# MotorDriver_Schematics.net
KiCad netlist of a schematic drawn in Altium Designer
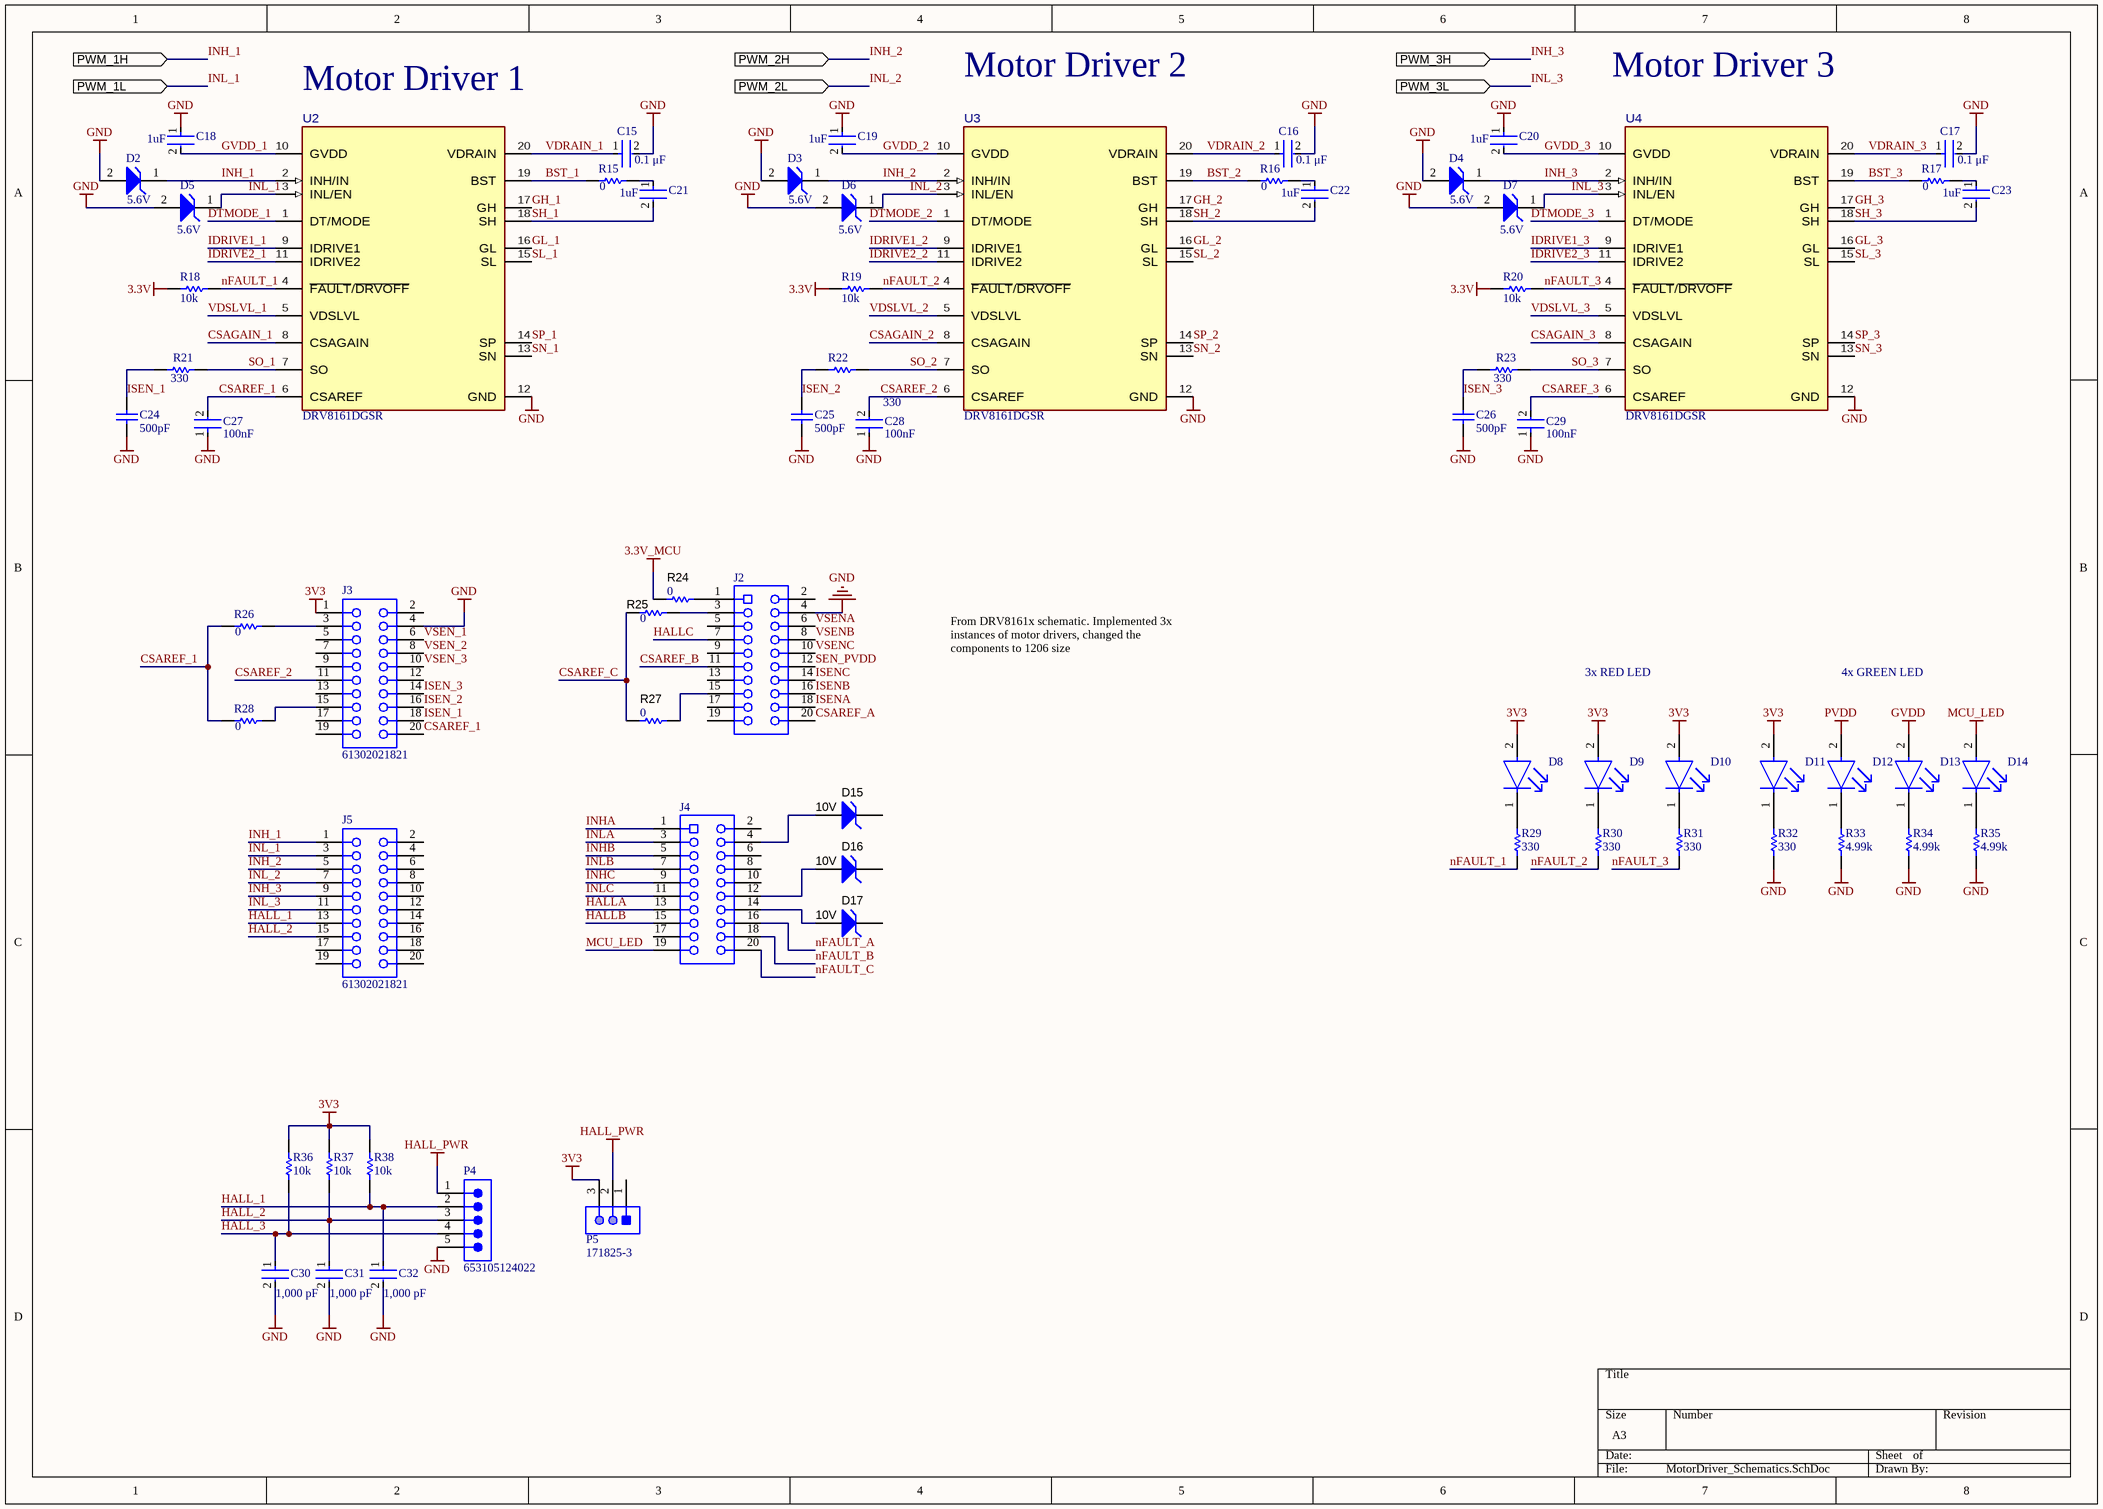
[diagram p0: MotorDriver_Schematics.SchDoc]

(export (version "E")
  (design (tool "Eeschema 10.0.6"))
  (components
    (comp (ref "C15")
      (value "C1206C104K1RACTU")
      (footprint "FP-C1206C-EB-MFG")
      (description "CAP CER 0.1UF 100V X7R 1206")
      (fields
        (field (name "TOLERANCE") "0.1")
        (field (name "OCTOPART") "https://octopart.com/c1206c104k1ractu-kemet-89521")
        (field (name "CAPACITANCE") "0.1 μF")
      )
      (libsource (lib "Altium Content Vault") (part "b4654b650e69147ec39a6b967a45e02"))
    )
    (comp (ref "C16")
      (value "C1206C104K1RACTU")
      (footprint "FP-C1206C-EB-MFG")
      (description "CAP CER 0.1UF 100V X7R 1206")
      (fields
        (field (name "TOLERANCE") "0.1")
        (field (name "OCTOPART") "https://octopart.com/c1206c104k1ractu-kemet-89521")
        (field (name "CAPACITANCE") "0.1 μF")
      )
      (libsource (lib "Altium Content Vault") (part "b4654b650e69147ec39a6b967a45e02"))
    )
    (comp (ref "C17")
      (value "C1206C104K1RACTU")
      (footprint "FP-C1206C-EB-MFG")
      (description "CAP CER 0.1UF 100V X7R 1206")
      (fields
        (field (name "TOLERANCE") "0.1")
        (field (name "OCTOPART") "https://octopart.com/c1206c104k1ractu-kemet-89521")
        (field (name "CAPACITANCE") "0.1 μF")
      )
      (libsource (lib "Altium Content Vault") (part "b4654b650e69147ec39a6b967a45e02"))
    )
    (comp (ref "C18")
      (value "12063C105KAT2A")
      (footprint "FP-1206-L_3_2_0_2-W_1_6_0-IPC_A")
      (description "General Purpose Ceramic Capacitor, 1206, 1uF, 10%, X7R, 15%, 25V")
      (fields
        (field (name "CAPACITANCE") "1uF")
        (field (name "TOLERANCE") "10%")
        (field (name "VOLTAGE") "25V")
      )
      (libsource (lib "Altium Content Vault") (part "b4654b650e69147ec39a6b967a45e02"))
    )
    (comp (ref "C19")
      (value "12063C105KAT2A")
      (footprint "FP-1206-L_3_2_0_2-W_1_6_0-IPC_A")
      (description "General Purpose Ceramic Capacitor, 1206, 1uF, 10%, X7R, 15%, 25V")
      (fields
        (field (name "CAPACITANCE") "1uF")
        (field (name "TOLERANCE") "10%")
        (field (name "VOLTAGE") "25V")
      )
      (libsource (lib "Altium Content Vault") (part "b4654b650e69147ec39a6b967a45e02"))
    )
    (comp (ref "C20")
      (value "12063C105KAT2A")
      (footprint "FP-1206-L_3_2_0_2-W_1_6_0-IPC_A")
      (description "General Purpose Ceramic Capacitor, 1206, 1uF, 10%, X7R, 15%, 25V")
      (fields
        (field (name "CAPACITANCE") "1uF")
        (field (name "TOLERANCE") "10%")
        (field (name "VOLTAGE") "25V")
      )
      (libsource (lib "Altium Content Vault") (part "b4654b650e69147ec39a6b967a45e02"))
    )
    (comp (ref "C21")
      (value "12063C105KAT2A")
      (footprint "FP-1206-L_3_2_0_2-W_1_6_0-IPC_A")
      (description "General Purpose Ceramic Capacitor, 1206, 1uF, 10%, X7R, 15%, 25V")
      (fields
        (field (name "CAPACITANCE") "1uF")
        (field (name "TOLERANCE") "10%")
        (field (name "VOLTAGE") "25V")
      )
      (libsource (lib "Altium Content Vault") (part "b4654b650e69147ec39a6b967a45e02"))
    )
    (comp (ref "C22")
      (value "12063C105KAT2A")
      (footprint "FP-1206-L_3_2_0_2-W_1_6_0-IPC_A")
      (description "General Purpose Ceramic Capacitor, 1206, 1uF, 10%, X7R, 15%, 25V")
      (fields
        (field (name "CAPACITANCE") "1uF")
        (field (name "TOLERANCE") "10%")
        (field (name "VOLTAGE") "25V")
      )
      (libsource (lib "Altium Content Vault") (part "b4654b650e69147ec39a6b967a45e02"))
    )
    (comp (ref "C23")
      (value "12063C105KAT2A")
      (footprint "FP-1206-L_3_2_0_2-W_1_6_0-IPC_A")
      (description "General Purpose Ceramic Capacitor, 1206, 1uF, 10%, X7R, 15%, 25V")
      (fields
        (field (name "CAPACITANCE") "1uF")
        (field (name "TOLERANCE") "10%")
        (field (name "VOLTAGE") "25V")
      )
      (libsource (lib "Altium Content Vault") (part "b4654b650e69147ec39a6b967a45e02"))
    )
    (comp (ref "C24")
      (value "04025C501KAT2A")
      (footprint "CAPC1005X56X25NL10T15")
      (fields (field (name "MANUFACTURER") "AVX Interconnect / Elco") (field (name "PARAMETER 1") "500pF"))
      (libsource (lib "Altium Content Vault") (part "CAP"))
    )
    (comp (ref "C25")
      (value "04025C501KAT2A")
      (footprint "CAPC1005X56X25NL10T15")
      (fields (field (name "MANUFACTURER") "AVX Interconnect / Elco") (field (name "PARAMETER 1") "500pF"))
      (libsource (lib "Altium Content Vault") (part "CAP"))
    )
    (comp (ref "C26")
      (value "04025C501KAT2A")
      (footprint "CAPC1005X56X25NL10T15")
      (fields (field (name "MANUFACTURER") "AVX Interconnect / Elco") (field (name "PARAMETER 1") "500pF"))
      (libsource (lib "Altium Content Vault") (part "CAP"))
    )
    (comp (ref "C27")
      (value "12061C104KAZ2A")
      (footprint "FP-1206-L_3_2_0_2-W_1_6_0-MFG")
      (description "General Purpose Ceramic Capacitor, 1206, 100nF, 10%, X7R, 15%, 100V")
      (fields (field (name "TOLERANCE") "10%") (field (name "CAPACITANCE") "100nF"))
      (libsource (lib "Altium Content Vault") (part "b4654b650e69147ec39a6b967a45e02"))
    )
    (comp (ref "C28")
      (value "12061C104KAZ2A")
      (footprint "FP-1206-L_3_2_0_2-W_1_6_0-MFG")
      (description "General Purpose Ceramic Capacitor, 1206, 100nF, 10%, X7R, 15%, 100V")
      (fields (field (name "TOLERANCE") "10%") (field (name "CAPACITANCE") "100nF"))
      (libsource (lib "Altium Content Vault") (part "b4654b650e69147ec39a6b967a45e02"))
    )
    (comp (ref "C29")
      (value "12061C104KAZ2A")
      (footprint "FP-1206-L_3_2_0_2-W_1_6_0-MFG")
      (description "General Purpose Ceramic Capacitor, 1206, 100nF, 10%, X7R, 15%, 100V")
      (fields (field (name "TOLERANCE") "10%") (field (name "CAPACITANCE") "100nF"))
      (libsource (lib "Altium Content Vault") (part "b4654b650e69147ec39a6b967a45e02"))
    )
    (comp (ref "C30")
      (value "C1206C102J1GACTU")
      (footprint "FP-C1206C-EB-MFG")
      (fields
        (field (name "CAPACITANCE") "1,000 pF")
        (field (name "OCTOPART") "https://octopart.com/c1206c102j1gactu-kemet-99808")
        (field (name "TOLERANCE") "0.05")
        (field (name "MANUFACTURER") "KEMET")
      )
      (libsource (lib "Altium Content Vault") (part "b4654b650e69147ec39a6b967a45e02"))
    )
    (comp (ref "C31")
      (value "C1206C102J1GACTU")
      (footprint "FP-C1206C-EB-MFG")
      (fields
        (field (name "CAPACITANCE") "1,000 pF")
        (field (name "OCTOPART") "https://octopart.com/c1206c102j1gactu-kemet-99808")
        (field (name "TOLERANCE") "0.05")
        (field (name "MANUFACTURER") "KEMET")
      )
      (libsource (lib "Altium Content Vault") (part "b4654b650e69147ec39a6b967a45e02"))
    )
    (comp (ref "C32")
      (value "C1206C102J1GACTU")
      (footprint "FP-C1206C-EB-MFG")
      (fields
        (field (name "CAPACITANCE") "1,000 pF")
        (field (name "OCTOPART") "https://octopart.com/c1206c102j1gactu-kemet-99808")
        (field (name "TOLERANCE") "0.05")
        (field (name "MANUFACTURER") "KEMET")
      )
      (libsource (lib "Altium Content Vault") (part "b4654b650e69147ec39a6b967a45e02"))
    )
    (comp (ref "D2")
      (value "MMSZ5232BT1G")
      (footprint "ONSC-SOD-123-2-425-04_V")
      (description "Zener Voltage Regulator, 500 mW, 2-Pin SOD-123, Pb-Free, Tape and Reel")
      (fields (field (name "MANUFACTURER") "On Semiconductor") (field (name "VZ TYP (V)") "5.6V"))
      (libsource (lib "Altium Content Vault") (part "ONSC-K1A2-2"))
    )
    (comp (ref "D3")
      (value "MMSZ5232BT1G")
      (footprint "ONSC-SOD-123-2-425-04_V")
      (description "Zener Voltage Regulator, 500 mW, 2-Pin SOD-123, Pb-Free, Tape and Reel")
      (fields (field (name "MANUFACTURER") "On Semiconductor") (field (name "VZ TYP (V)") "5.6V"))
      (libsource (lib "Altium Content Vault") (part "ONSC-K1A2-2"))
    )
    (comp (ref "D4")
      (value "MMSZ5232BT1G")
      (footprint "ONSC-SOD-123-2-425-04_V")
      (description "Zener Voltage Regulator, 500 mW, 2-Pin SOD-123, Pb-Free, Tape and Reel")
      (fields (field (name "MANUFACTURER") "On Semiconductor") (field (name "VZ TYP (V)") "5.6V"))
      (libsource (lib "Altium Content Vault") (part "ONSC-K1A2-2"))
    )
    (comp (ref "D5")
      (value "MMSZ5232BT1G")
      (footprint "ONSC-SOD-123-2-425-04_V")
      (description "Zener Voltage Regulator, 500 mW, 2-Pin SOD-123, Pb-Free, Tape and Reel")
      (fields (field (name "MANUFACTURER") "On Semiconductor") (field (name "VZ TYP (V)") "5.6V"))
      (libsource (lib "Altium Content Vault") (part "ONSC-K1A2-2"))
    )
    (comp (ref "D6")
      (value "MMSZ5232BT1G")
      (footprint "ONSC-SOD-123-2-425-04_V")
      (description "Zener Voltage Regulator, 500 mW, 2-Pin SOD-123, Pb-Free, Tape and Reel")
      (fields (field (name "MANUFACTURER") "On Semiconductor") (field (name "VZ TYP (V)") "5.6V"))
      (libsource (lib "Altium Content Vault") (part "ONSC-K1A2-2"))
    )
    (comp (ref "D7")
      (value "MMSZ5232BT1G")
      (footprint "ONSC-SOD-123-2-425-04_V")
      (description "Zener Voltage Regulator, 500 mW, 2-Pin SOD-123, Pb-Free, Tape and Reel")
      (fields (field (name "MANUFACTURER") "On Semiconductor") (field (name "VZ TYP (V)") "5.6V"))
      (libsource (lib "Altium Content Vault") (part "ONSC-K1A2-2"))
    )
    (comp (ref "D8")
      (value "HSMS-C150")
      (footprint "FP-HSMS-C150-MFG")
      (description "LED RED DIFFUSED CHIP SMD")
      (libsource (lib "Altium Content Vault") (part "8706943c75ba83719d021d2fdc84c58"))
    )
    (comp (ref "D9")
      (value "HSMS-C150")
      (footprint "FP-HSMS-C150-MFG")
      (description "LED RED DIFFUSED CHIP SMD")
      (libsource (lib "Altium Content Vault") (part "8706943c75ba83719d021d2fdc84c58"))
    )
    (comp (ref "D10")
      (value "HSMS-C150")
      (footprint "FP-HSMS-C150-MFG")
      (description "LED RED DIFFUSED CHIP SMD")
      (libsource (lib "Altium Content Vault") (part "8706943c75ba83719d021d2fdc84c58"))
    )
    (comp (ref "D11")
      (value "LTST-C171GKT")
      (footprint "FP-LTST-C171GKT-MFG")
      (description "LED GREEN CLEAR CHIP SMD")
      (libsource (lib "Altium Content Vault") (part "8706943c75ba83719d021d2fdc84c58"))
    )
    (comp (ref "D12")
      (value "LTST-C171GKT")
      (footprint "FP-LTST-C171GKT-MFG")
      (description "LED GREEN CLEAR CHIP SMD")
      (libsource (lib "Altium Content Vault") (part "8706943c75ba83719d021d2fdc84c58"))
    )
    (comp (ref "D13")
      (value "LTST-C171GKT")
      (footprint "FP-LTST-C171GKT-MFG")
      (description "LED GREEN CLEAR CHIP SMD")
      (libsource (lib "Altium Content Vault") (part "8706943c75ba83719d021d2fdc84c58"))
    )
    (comp (ref "D14")
      (value "LTST-C171GKT")
      (footprint "FP-LTST-C171GKT-MFG")
      (description "LED GREEN CLEAR CHIP SMD")
      (libsource (lib "Altium Content Vault") (part "8706943c75ba83719d021d2fdc84c58"))
    )
    (comp (ref "D15")
      (value "10V")
      (footprint "SOD-123")
      (description "Diode, Zener, 10 V, 500 mW, SOD-123")
      (fields (field (name "MANUFACTURER") "Diodes Inc.") (field (name "PARTNUMBER") "DDZ10C-7"))
      (libsource (lib "Altium Vault - TI") (part "Zener"))
    )
    (comp (ref "D16")
      (value "10V")
      (footprint "SOD-123")
      (description "Diode, Zener, 10 V, 500 mW, SOD-123")
      (fields (field (name "MANUFACTURER") "Diodes Inc.") (field (name "PARTNUMBER") "DDZ10C-7"))
      (libsource (lib "Altium Vault - TI") (part "Zener"))
    )
    (comp (ref "D17")
      (value "10V")
      (footprint "SOD-123")
      (description "Diode, Zener, 10 V, 500 mW, SOD-123")
      (fields (field (name "MANUFACTURER") "Diodes Inc.") (field (name "PARTNUMBER") "DDZ10C-7"))
      (libsource (lib "Altium Vault - TI") (part "Zener"))
    )
    (comp (ref "J2")
      (value "SSQ-110-03-G-D")
      (footprint "Samtec_SSQ-110-03-x-D")
      (description "Receptacle, 2.54mm, 10x2, Gold, TH")
      (fields (field (name "MANUFACTURER") "Samtec") (field (name "PUBLISHER") "Texas Instruments"))
      (libsource (lib "Altium Vault - TI") (part "Receptacle_10x2"))
    )
    (comp (ref "J3")
      (value "61302021821")
      (footprint "61302021821")
      (libsource (lib "Altium Content Vault") (part "Header_Female_2R_20P"))
    )
    (comp (ref "J4")
      (value "SSQ-110-03-G-D")
      (footprint "Samtec_SSQ-110-03-x-D")
      (description "Receptacle, 2.54mm, 10x2, Gold, TH")
      (fields (field (name "MANUFACTURER") "Samtec") (field (name "PUBLISHER") "Texas Instruments"))
      (libsource (lib "Altium Vault - TI") (part "Receptacle_10x2"))
    )
    (comp (ref "J5")
      (value "61302021821")
      (footprint "61302021821")
      (libsource (lib "Altium Content Vault") (part "Header_Female_2R_20P"))
    )
    (comp (ref "P4")
      (value "653105124022")
      (footprint "653105124022")
      (libsource (lib "Altium Content Vault") (part "Header_Male_1R_05P"))
    )
    (comp (ref "P5")
      (value "171825-3")
      (footprint "TECO-171825-3_V")
      (fields (field (name "MANUFACTURER") "TE Connectivity"))
      (libsource (lib "Altium Content Vault") (part "CN-1P-M-R3"))
    )
    (comp (ref "R15")
      (value "ERJ-8GEY0R00V")
      (footprint "RESC3216X70X50NL05T20")
      (fields (field (name "MANUFACTURER") "Panasonic") (field (name "RESISTANCE") "0"))
      (libsource (lib "Altium Content Vault") (part "RES"))
    )
    (comp (ref "R16")
      (value "ERJ-8GEY0R00V")
      (footprint "RESC3216X70X50NL05T20")
      (fields (field (name "MANUFACTURER") "Panasonic") (field (name "RESISTANCE") "0"))
      (libsource (lib "Altium Content Vault") (part "RES"))
    )
    (comp (ref "R17")
      (value "ERJ-8GEY0R00V")
      (footprint "RESC3216X70X50NL05T20")
      (fields (field (name "MANUFACTURER") "Panasonic") (field (name "RESISTANCE") "0"))
      (libsource (lib "Altium Content Vault") (part "RES"))
    )
    (comp (ref "R18")
      (value "CRCW120610K0FKEAHP")
      (footprint "RESC3116X65X50NL20T20")
      (fields (field (name "MANUFACTURER") "Vishay Dale") (field (name "RESISTANCE") "10k"))
      (libsource (lib "Altium Content Vault") (part "RES"))
    )
    (comp (ref "R19")
      (value "CRCW120610K0FKEAHP")
      (footprint "RESC3116X65X50NL20T20")
      (fields (field (name "MANUFACTURER") "Vishay Dale") (field (name "RESISTANCE") "10k"))
      (libsource (lib "Altium Content Vault") (part "RES"))
    )
    (comp (ref "R20")
      (value "CRCW120610K0FKEAHP")
      (footprint "RESC3116X65X50NL20T20")
      (fields (field (name "MANUFACTURER") "Vishay Dale") (field (name "RESISTANCE") "10k"))
      (libsource (lib "Altium Content Vault") (part "RES"))
    )
    (comp (ref "R21")
      (value "ERJ-8GEYJ331V")
      (footprint "RESC3216X70X50NL05T20")
      (fields (field (name "MANUFACTURER") "Panasonic") (field (name "RESISTANCE") "330"))
      (libsource (lib "Altium Content Vault") (part "RES"))
    )
    (comp (ref "R22")
      (value "ERJ-8GEYJ331V")
      (footprint "RESC3216X70X50NL05T20")
      (fields (field (name "MANUFACTURER") "Panasonic") (field (name "RESISTANCE") "330"))
      (libsource (lib "Altium Content Vault") (part "RES"))
    )
    (comp (ref "R23")
      (value "ERJ-8GEYJ331V")
      (footprint "RESC3216X70X50NL05T20")
      (fields (field (name "MANUFACTURER") "Panasonic") (field (name "RESISTANCE") "330"))
      (libsource (lib "Altium Content Vault") (part "RES"))
    )
    (comp (ref "R24")
      (value "CRCW06030000Z0EA")
      (footprint "0603L")
      (description "RES, 0, 5%, 0.1 W, AEC-Q200 Grade 0, 0603")
      (fields (field (name "MANUFACTURER") "Vishay-Dale") (field (name "VALUEDISPLAYED") "0"))
      (libsource (lib "Altium Vault - TI") (part "Resistor"))
    )
    (comp (ref "R25")
      (value "CRCW06030000Z0EA")
      (footprint "0603L")
      (description "RES, 0, 5%, 0.1 W, AEC-Q200 Grade 0, 0603")
      (fields (field (name "MANUFACTURER") "Vishay-Dale") (field (name "VALUEDISPLAYED") "0"))
      (libsource (lib "Altium Vault - TI") (part "Resistor"))
    )
    (comp (ref "R26")
      (value "ERJ-8GEY0R00V")
      (footprint "RESC3216X70X50NL05T20")
      (fields (field (name "MANUFACTURER") "Panasonic") (field (name "RESISTANCE") "0"))
      (libsource (lib "Altium Content Vault") (part "RES"))
    )
    (comp (ref "R27")
      (value "CRCW06030000Z0EA")
      (footprint "0603L")
      (description "RES, 0, 5%, 0.1 W, AEC-Q200 Grade 0, 0603")
      (fields (field (name "MANUFACTURER") "Vishay-Dale") (field (name "VALUEDISPLAYED") "0"))
      (libsource (lib "Altium Vault - TI") (part "Resistor"))
    )
    (comp (ref "R28")
      (value "ERJ-8GEY0R00V")
      (footprint "RESC3216X70X50NL05T20")
      (fields (field (name "MANUFACTURER") "Panasonic") (field (name "RESISTANCE") "0"))
      (libsource (lib "Altium Content Vault") (part "RES"))
    )
    (comp (ref "R29")
      (value "ERJ-8GEYJ331V")
      (footprint "RESC3216X70X50NL05T20")
      (fields (field (name "MANUFACTURER") "Panasonic") (field (name "RESISTANCE") "330"))
      (libsource (lib "Altium Content Vault") (part "RES"))
    )
    (comp (ref "R30")
      (value "ERJ-8GEYJ331V")
      (footprint "RESC3216X70X50NL05T20")
      (fields (field (name "MANUFACTURER") "Panasonic") (field (name "RESISTANCE") "330"))
      (libsource (lib "Altium Content Vault") (part "RES"))
    )
    (comp (ref "R31")
      (value "ERJ-8GEYJ331V")
      (footprint "RESC3216X70X50NL05T20")
      (fields (field (name "MANUFACTURER") "Panasonic") (field (name "RESISTANCE") "330"))
      (libsource (lib "Altium Content Vault") (part "RES"))
    )
    (comp (ref "R32")
      (value "ERJ-8GEYJ331V")
      (footprint "RESC3216X70X50NL05T20")
      (fields (field (name "MANUFACTURER") "Panasonic") (field (name "RESISTANCE") "330"))
      (libsource (lib "Altium Content Vault") (part "RES"))
    )
    (comp (ref "R33")
      (value "CRCW12064K99FKEA")
      (footprint "RESC3216X60X45ML10T20")
      (fields (field (name "MANUFACTURER") "Vishay Dale") (field (name "RESISTANCE") "4.99k"))
      (libsource (lib "Altium Content Vault") (part "RES"))
    )
    (comp (ref "R34")
      (value "CRCW12064K99FKEA")
      (footprint "RESC3216X60X45ML10T20")
      (fields (field (name "MANUFACTURER") "Vishay Dale") (field (name "RESISTANCE") "4.99k"))
      (libsource (lib "Altium Content Vault") (part "RES"))
    )
    (comp (ref "R35")
      (value "CRCW12064K99FKEA")
      (footprint "RESC3216X60X45ML10T20")
      (fields (field (name "MANUFACTURER") "Vishay Dale") (field (name "RESISTANCE") "4.99k"))
      (libsource (lib "Altium Content Vault") (part "RES"))
    )
    (comp (ref "R36")
      (value "CRCW120610K0FKEAHP")
      (footprint "RESC3116X65X50NL20T20")
      (fields (field (name "MANUFACTURER") "Vishay Dale") (field (name "RESISTANCE") "10k"))
      (libsource (lib "Altium Content Vault") (part "RES"))
    )
    (comp (ref "R37")
      (value "CRCW120610K0FKEAHP")
      (footprint "RESC3116X65X50NL20T20")
      (fields (field (name "MANUFACTURER") "Vishay Dale") (field (name "RESISTANCE") "10k"))
      (libsource (lib "Altium Content Vault") (part "RES"))
    )
    (comp (ref "R38")
      (value "CRCW120610K0FKEAHP")
      (footprint "RESC3116X65X50NL20T20")
      (fields (field (name "MANUFACTURER") "Vishay Dale") (field (name "RESISTANCE") "10k"))
      (libsource (lib "Altium Content Vault") (part "RES"))
    )
    (comp (ref "U2")
      (value "DRV8161DGSR")
      (footprint "DGS0020A-MFG")
      (description "100-V Half-Bridge Smart Gate Driver")
      (fields (field (name "MANUFACTURER") "Texas Instruments") (field (name "PARTNUMBER") "DRV8161DGSR"))
      (libsource (lib "Altium Vault - TI") (part "SYM-DRV8161DGSR"))
    )
    (comp (ref "U3")
      (value "DRV8161DGSR")
      (footprint "DGS0020A-MFG")
      (description "100-V Half-Bridge Smart Gate Driver")
      (fields (field (name "MANUFACTURER") "Texas Instruments") (field (name "PARTNUMBER") "DRV8161DGSR"))
      (libsource (lib "Altium Vault - TI") (part "SYM-DRV8161DGSR"))
    )
    (comp (ref "U4")
      (value "DRV8161DGSR")
      (footprint "DGS0020A-MFG")
      (description "100-V Half-Bridge Smart Gate Driver")
      (fields (field (name "MANUFACTURER") "Texas Instruments") (field (name "PARTNUMBER") "DRV8161DGSR"))
      (libsource (lib "Altium Vault - TI") (part "SYM-DRV8161DGSR"))
    )
  )
  (nets
    (net (code "1") (name "/BST_1") (class "Default")
      (node (ref "R15") (pin "1") (pinfunction "1_1") (pintype "passive"))
      (node (ref "U2") (pin "19") (pinfunction "BST_19") (pintype "passive"))
    )
    (net (code "2") (name "/BST_2") (class "Default")
      (node (ref "R16") (pin "1") (pinfunction "1_1") (pintype "passive"))
      (node (ref "U3") (pin "19") (pinfunction "BST_19") (pintype "passive"))
    )
    (net (code "3") (name "/BST_3") (class "Default")
      (node (ref "R17") (pin "1") (pinfunction "1_1") (pintype "passive"))
      (node (ref "U4") (pin "19") (pinfunction "BST_19") (pintype "passive"))
    )
    (net (code "4") (name "/CSAGAIN_1") (class "Default")
      (node (ref "U2") (pin "8") (pinfunction "CSAGAIN_8") (pintype "passive"))
    )
    (net (code "5") (name "/CSAGAIN_2") (class "Default")
      (node (ref "U3") (pin "8") (pinfunction "CSAGAIN_8") (pintype "passive"))
    )
    (net (code "6") (name "/CSAGAIN_3") (class "Default")
      (node (ref "U4") (pin "8") (pinfunction "CSAGAIN_8") (pintype "passive"))
    )
    (net (code "7") (name "/CSAREF_1") (class "Default")
      (node (ref "C27") (pin "2") (pinfunction "2_2") (pintype "passive"))
      (node (ref "J3") (pin "20") (pinfunction "20_20") (pintype "passive"))
      (node (ref "R26") (pin "1") (pinfunction "1_1") (pintype "passive"))
      (node (ref "R28") (pin "1") (pinfunction "1_1") (pintype "passive"))
      (node (ref "U2") (pin "6") (pinfunction "CSAREF_6") (pintype "passive"))
    )
    (net (code "8") (name "/CSAREF_2") (class "Default")
      (node (ref "C28") (pin "2") (pinfunction "2_2") (pintype "passive"))
      (node (ref "J3") (pin "11") (pinfunction "11_11") (pintype "passive"))
      (node (ref "U3") (pin "6") (pinfunction "CSAREF_6") (pintype "passive"))
    )
    (net (code "9") (name "/CSAREF_3") (class "Default")
      (node (ref "C29") (pin "2") (pinfunction "2_2") (pintype "passive"))
      (node (ref "U4") (pin "6") (pinfunction "CSAREF_6") (pintype "passive"))
    )
    (net (code "10") (name "/CSAREF_A") (class "Default")
      (node (ref "J2") (pin "20") (pinfunction "20_20") (pintype "passive"))
    )
    (net (code "11") (name "/CSAREF_B") (class "Default")
      (node (ref "J2") (pin "11") (pinfunction "11_11") (pintype "passive"))
    )
    (net (code "12") (name "/CSAREF_C") (class "Default")
      (node (ref "R25") (pin "1") (pinfunction "1_1") (pintype "passive"))
      (node (ref "R27") (pin "1") (pinfunction "1_1") (pintype "passive"))
    )
    (net (code "13") (name "/DTMODE_1") (class "Default")
      (node (ref "U2") (pin "1") (pinfunction "DT/MODE_1") (pintype "passive"))
    )
    (net (code "14") (name "/DTMODE_2") (class "Default")
      (node (ref "U3") (pin "1") (pinfunction "DT/MODE_1") (pintype "passive"))
    )
    (net (code "15") (name "/DTMODE_3") (class "Default")
      (node (ref "U4") (pin "1") (pinfunction "DT/MODE_1") (pintype "passive"))
    )
    (net (code "16") (name "/GH_1") (class "Default")
      (node (ref "U2") (pin "17") (pinfunction "GH_17") (pintype "passive"))
    )
    (net (code "17") (name "/GH_2") (class "Default")
      (node (ref "U3") (pin "17") (pinfunction "GH_17") (pintype "passive"))
    )
    (net (code "18") (name "/GH_3") (class "Default")
      (node (ref "U4") (pin "17") (pinfunction "GH_17") (pintype "passive"))
    )
    (net (code "19") (name "/GL_1") (class "Default")
      (node (ref "U2") (pin "16") (pinfunction "GL_16") (pintype "passive"))
    )
    (net (code "20") (name "/GL_2") (class "Default")
      (node (ref "U3") (pin "16") (pinfunction "GL_16") (pintype "passive"))
    )
    (net (code "21") (name "/GL_3") (class "Default")
      (node (ref "U4") (pin "16") (pinfunction "GL_16") (pintype "passive"))
    )
    (net (code "22") (name "/GVDD_1") (class "Default")
      (node (ref "C18") (pin "2") (pinfunction "2_2") (pintype "passive"))
      (node (ref "U2") (pin "10") (pinfunction "GVDD_10") (pintype "power_in"))
    )
    (net (code "23") (name "/GVDD_2") (class "Default")
      (node (ref "C19") (pin "2") (pinfunction "2_2") (pintype "passive"))
      (node (ref "U3") (pin "10") (pinfunction "GVDD_10") (pintype "power_in"))
    )
    (net (code "24") (name "/GVDD_3") (class "Default")
      (node (ref "C20") (pin "2") (pinfunction "2_2") (pintype "passive"))
      (node (ref "U4") (pin "10") (pinfunction "GVDD_10") (pintype "power_in"))
    )
    (net (code "25") (name "/HALLA") (class "Default")
      (node (ref "J4") (pin "13") (pinfunction "13_13") (pintype "passive"))
    )
    (net (code "26") (name "/HALLB") (class "Default")
      (node (ref "J4") (pin "15") (pinfunction "15_15") (pintype "passive"))
    )
    (net (code "27") (name "/HALLC") (class "Default")
      (node (ref "J2") (pin "7") (pinfunction "7_7") (pintype "passive"))
    )
    (net (code "28") (name "/HALL_1") (class "Default")
      (node (ref "C32") (pin "1") (pinfunction "1_1") (pintype "passive"))
      (node (ref "J5") (pin "13") (pinfunction "13_13") (pintype "passive"))
      (node (ref "P4") (pin "2") (pinfunction "2_2") (pintype "passive"))
      (node (ref "R38") (pin "1") (pinfunction "1_1") (pintype "passive"))
    )
    (net (code "29") (name "/HALL_2") (class "Default")
      (node (ref "C31") (pin "1") (pinfunction "1_1") (pintype "passive"))
      (node (ref "J5") (pin "15") (pinfunction "15_15") (pintype "passive"))
      (node (ref "P4") (pin "3") (pinfunction "3_3") (pintype "passive"))
      (node (ref "R37") (pin "1") (pinfunction "1_1") (pintype "passive"))
    )
    (net (code "30") (name "/HALL_3") (class "Default")
      (node (ref "C30") (pin "1") (pinfunction "1_1") (pintype "passive"))
      (node (ref "P4") (pin "4") (pinfunction "4_4") (pintype "passive"))
      (node (ref "R36") (pin "1") (pinfunction "1_1") (pintype "passive"))
    )
    (net (code "31") (name "/IDRIVE1_1") (class "Default")
      (node (ref "U2") (pin "9") (pinfunction "IDRIVE1_9") (pintype "passive"))
    )
    (net (code "32") (name "/IDRIVE1_2") (class "Default")
      (node (ref "U3") (pin "9") (pinfunction "IDRIVE1_9") (pintype "passive"))
    )
    (net (code "33") (name "/IDRIVE1_3") (class "Default")
      (node (ref "U4") (pin "9") (pinfunction "IDRIVE1_9") (pintype "passive"))
    )
    (net (code "34") (name "/IDRIVE2_1") (class "Default")
      (node (ref "U2") (pin "11") (pinfunction "IDRIVE2_11") (pintype "passive"))
    )
    (net (code "35") (name "/IDRIVE2_2") (class "Default")
      (node (ref "U3") (pin "11") (pinfunction "IDRIVE2_11") (pintype "passive"))
    )
    (net (code "36") (name "/IDRIVE2_3") (class "Default")
      (node (ref "U4") (pin "11") (pinfunction "IDRIVE2_11") (pintype "passive"))
    )
    (net (code "37") (name "/INHA") (class "Default")
      (node (ref "J4") (pin "1") (pinfunction "1_1") (pintype "passive"))
    )
    (net (code "38") (name "/INHB") (class "Default")
      (node (ref "J4") (pin "5") (pinfunction "5_5") (pintype "passive"))
    )
    (net (code "39") (name "/INHC") (class "Default")
      (node (ref "J4") (pin "9") (pinfunction "9_9") (pintype "passive"))
    )
    (net (code "40") (name "/INH_1") (class "Default")
      (node (ref "D2") (pin "1") (pinfunction "K_1") (pintype "passive"))
      (node (ref "J5") (pin "1") (pinfunction "1_1") (pintype "passive"))
      (node (ref "U2") (pin "2") (pinfunction "INH/IN_2") (pintype "input"))
    )
    (net (code "41") (name "/INH_2") (class "Default")
      (node (ref "D3") (pin "1") (pinfunction "K_1") (pintype "passive"))
      (node (ref "J5") (pin "5") (pinfunction "5_5") (pintype "passive"))
      (node (ref "U3") (pin "2") (pinfunction "INH/IN_2") (pintype "input"))
    )
    (net (code "42") (name "/INH_3") (class "Default")
      (node (ref "D4") (pin "1") (pinfunction "K_1") (pintype "passive"))
      (node (ref "J5") (pin "9") (pinfunction "9_9") (pintype "passive"))
      (node (ref "U4") (pin "2") (pinfunction "INH/IN_2") (pintype "input"))
    )
    (net (code "43") (name "/INLA") (class "Default")
      (node (ref "J4") (pin "3") (pinfunction "3_3") (pintype "passive"))
    )
    (net (code "44") (name "/INLB") (class "Default")
      (node (ref "J4") (pin "7") (pinfunction "7_7") (pintype "passive"))
    )
    (net (code "45") (name "/INLC") (class "Default")
      (node (ref "J4") (pin "11") (pinfunction "11_11") (pintype "passive"))
    )
    (net (code "46") (name "/INL_1") (class "Default")
      (node (ref "D5") (pin "1") (pinfunction "K_1") (pintype "passive"))
      (node (ref "J5") (pin "3") (pinfunction "3_3") (pintype "passive"))
      (node (ref "U2") (pin "3") (pinfunction "INL/EN_3") (pintype "input"))
    )
    (net (code "47") (name "/INL_2") (class "Default")
      (node (ref "D6") (pin "1") (pinfunction "K_1") (pintype "passive"))
      (node (ref "J5") (pin "7") (pinfunction "7_7") (pintype "passive"))
      (node (ref "U3") (pin "3") (pinfunction "INL/EN_3") (pintype "input"))
    )
    (net (code "48") (name "/INL_3") (class "Default")
      (node (ref "D7") (pin "1") (pinfunction "K_1") (pintype "passive"))
      (node (ref "J5") (pin "11") (pinfunction "11_11") (pintype "passive"))
      (node (ref "U4") (pin "3") (pinfunction "INL/EN_3") (pintype "input"))
    )
    (net (code "49") (name "/ISENA") (class "Default")
      (node (ref "J2") (pin "18") (pinfunction "18_18") (pintype "passive"))
    )
    (net (code "50") (name "/ISENB") (class "Default")
      (node (ref "J2") (pin "16") (pinfunction "16_16") (pintype "passive"))
    )
    (net (code "51") (name "/ISENC") (class "Default")
      (node (ref "J2") (pin "14") (pinfunction "14_14") (pintype "passive"))
    )
    (net (code "52") (name "/ISEN_1") (class "Default")
      (node (ref "C24") (pin "2") (pinfunction "2_2") (pintype "passive"))
      (node (ref "J3") (pin "18") (pinfunction "18_18") (pintype "passive"))
      (node (ref "R21") (pin "1") (pinfunction "1_1") (pintype "passive"))
    )
    (net (code "53") (name "/ISEN_2") (class "Default")
      (node (ref "C25") (pin "2") (pinfunction "2_2") (pintype "passive"))
      (node (ref "J3") (pin "16") (pinfunction "16_16") (pintype "passive"))
      (node (ref "R22") (pin "2") (pinfunction "2_2") (pintype "passive"))
    )
    (net (code "54") (name "/ISEN_3") (class "Default")
      (node (ref "C26") (pin "2") (pinfunction "2_2") (pintype "passive"))
      (node (ref "J3") (pin "14") (pinfunction "14_14") (pintype "passive"))
      (node (ref "R23") (pin "1") (pinfunction "1_1") (pintype "passive"))
    )
    (net (code "55") (name "/SEN_PVDD") (class "Default")
      (node (ref "J2") (pin "12") (pinfunction "12_12") (pintype "passive"))
    )
    (net (code "56") (name "/SH_1") (class "Default")
      (node (ref "C21") (pin "2") (pinfunction "2_2") (pintype "passive"))
      (node (ref "U2") (pin "18") (pinfunction "SH_18") (pintype "passive"))
    )
    (net (code "57") (name "/SH_2") (class "Default")
      (node (ref "C22") (pin "2") (pinfunction "2_2") (pintype "passive"))
      (node (ref "U3") (pin "18") (pinfunction "SH_18") (pintype "passive"))
    )
    (net (code "58") (name "/SH_3") (class "Default")
      (node (ref "C23") (pin "2") (pinfunction "2_2") (pintype "passive"))
      (node (ref "U4") (pin "18") (pinfunction "SH_18") (pintype "passive"))
    )
    (net (code "59") (name "/SL_1") (class "Default")
      (node (ref "U2") (pin "15") (pinfunction "SL_15") (pintype "passive"))
    )
    (net (code "60") (name "/SL_2") (class "Default")
      (node (ref "U3") (pin "15") (pinfunction "SL_15") (pintype "passive"))
    )
    (net (code "61") (name "/SL_3") (class "Default")
      (node (ref "U4") (pin "15") (pinfunction "SL_15") (pintype "passive"))
    )
    (net (code "62") (name "/SN_1") (class "Default")
      (node (ref "U2") (pin "13") (pinfunction "SN_13") (pintype "passive"))
    )
    (net (code "63") (name "/SN_2") (class "Default")
      (node (ref "U3") (pin "13") (pinfunction "SN_13") (pintype "passive"))
    )
    (net (code "64") (name "/SN_3") (class "Default")
      (node (ref "U4") (pin "13") (pinfunction "SN_13") (pintype "passive"))
    )
    (net (code "65") (name "/SO_1") (class "Default")
      (node (ref "R21") (pin "2") (pinfunction "2_2") (pintype "passive"))
      (node (ref "U2") (pin "7") (pinfunction "SO_7") (pintype "passive"))
    )
    (net (code "66") (name "/SO_2") (class "Default")
      (node (ref "R22") (pin "1") (pinfunction "1_1") (pintype "passive"))
      (node (ref "U3") (pin "7") (pinfunction "SO_7") (pintype "passive"))
    )
    (net (code "67") (name "/SO_3") (class "Default")
      (node (ref "R23") (pin "2") (pinfunction "2_2") (pintype "passive"))
      (node (ref "U4") (pin "7") (pinfunction "SO_7") (pintype "passive"))
    )
    (net (code "68") (name "/SP_1") (class "Default")
      (node (ref "U2") (pin "14") (pinfunction "SP_14") (pintype "passive"))
    )
    (net (code "69") (name "/SP_2") (class "Default")
      (node (ref "U3") (pin "14") (pinfunction "SP_14") (pintype "passive"))
    )
    (net (code "70") (name "/SP_3") (class "Default")
      (node (ref "U4") (pin "14") (pinfunction "SP_14") (pintype "passive"))
    )
    (net (code "71") (name "/VDRAIN_1") (class "Default")
      (node (ref "C15") (pin "1") (pinfunction "1_1") (pintype "passive"))
      (node (ref "U2") (pin "20") (pinfunction "VDRAIN_20") (pintype "power_in"))
    )
    (net (code "72") (name "/VDRAIN_2") (class "Default")
      (node (ref "C16") (pin "1") (pinfunction "1_1") (pintype "passive"))
      (node (ref "U3") (pin "20") (pinfunction "VDRAIN_20") (pintype "power_in"))
    )
    (net (code "73") (name "/VDRAIN_3") (class "Default")
      (node (ref "C17") (pin "1") (pinfunction "1_1") (pintype "passive"))
      (node (ref "U4") (pin "20") (pinfunction "VDRAIN_20") (pintype "power_in"))
    )
    (net (code "74") (name "/VDSLVL_1") (class "Default")
      (node (ref "U2") (pin "5") (pinfunction "VDSLVL_5") (pintype "passive"))
    )
    (net (code "75") (name "/VDSLVL_2") (class "Default")
      (node (ref "U3") (pin "5") (pinfunction "VDSLVL_5") (pintype "passive"))
    )
    (net (code "76") (name "/VDSLVL_3") (class "Default")
      (node (ref "U4") (pin "5") (pinfunction "VDSLVL_5") (pintype "passive"))
    )
    (net (code "77") (name "/VSENA") (class "Default")
      (node (ref "J2") (pin "6") (pinfunction "6_6") (pintype "passive"))
    )
    (net (code "78") (name "/VSENB") (class "Default")
      (node (ref "J2") (pin "8") (pinfunction "8_8") (pintype "passive"))
    )
    (net (code "79") (name "/VSENC") (class "Default")
      (node (ref "J2") (pin "10") (pinfunction "10_10") (pintype "passive"))
    )
    (net (code "80") (name "/VSEN_1") (class "Default")
      (node (ref "J3") (pin "6") (pinfunction "6_6") (pintype "passive"))
    )
    (net (code "81") (name "/VSEN_2") (class "Default")
      (node (ref "J3") (pin "8") (pinfunction "8_8") (pintype "passive"))
    )
    (net (code "82") (name "/VSEN_3") (class "Default")
      (node (ref "J3") (pin "10") (pinfunction "10_10") (pintype "passive"))
    )
    (net (code "83") (name "/nFAULT_1") (class "Default")
      (node (ref "R18") (pin "2") (pinfunction "2_2") (pintype "passive"))
      (node (ref "R29") (pin "1") (pinfunction "1_1") (pintype "passive"))
      (node (ref "U2") (pin "4") (pinfunction "~{FAULT}/~{DRVOFF}_4") (pintype "passive"))
    )
    (net (code "84") (name "/nFAULT_2") (class "Default")
      (node (ref "R19") (pin "2") (pinfunction "2_2") (pintype "passive"))
      (node (ref "R30") (pin "1") (pinfunction "1_1") (pintype "passive"))
      (node (ref "U3") (pin "4") (pinfunction "~{FAULT}/~{DRVOFF}_4") (pintype "passive"))
    )
    (net (code "85") (name "/nFAULT_3") (class "Default")
      (node (ref "R20") (pin "2") (pinfunction "2_2") (pintype "passive"))
      (node (ref "R31") (pin "1") (pinfunction "1_1") (pintype "passive"))
      (node (ref "U4") (pin "4") (pinfunction "~{FAULT}/~{DRVOFF}_4") (pintype "passive"))
    )
    (net (code "86") (name "/nFAULT_A") (class "Default")
      (node (ref "J4") (pin "16") (pinfunction "16_16") (pintype "passive"))
    )
    (net (code "87") (name "/nFAULT_B") (class "Default")
      (node (ref "J4") (pin "18") (pinfunction "18_18") (pintype "passive"))
    )
    (net (code "88") (name "/nFAULT_C") (class "Default")
      (node (ref "J4") (pin "20") (pinfunction "20_20") (pintype "passive"))
    )
    (net (code "89") (name "3.3V") (class "Default")
      (node (ref "R18") (pin "1") (pinfunction "1_1") (pintype "passive"))
      (node (ref "R19") (pin "1") (pinfunction "1_1") (pintype "passive"))
      (node (ref "R20") (pin "1") (pinfunction "1_1") (pintype "passive"))
    )
    (net (code "90") (name "3.3V_MCU") (class "Default")
      (node (ref "R24") (pin "1") (pinfunction "1_1") (pintype "passive"))
    )
    (net (code "91") (name "3V3") (class "Default")
      (node (ref "D10") (pin "2") (pinfunction "A_2") (pintype "passive"))
      (node (ref "D11") (pin "2") (pinfunction "A_2") (pintype "passive"))
      (node (ref "D8") (pin "2") (pinfunction "A_2") (pintype "passive"))
      (node (ref "D9") (pin "2") (pinfunction "A_2") (pintype "passive"))
      (node (ref "J3") (pin "1") (pinfunction "1_1") (pintype "passive"))
      (node (ref "P5") (pin "3") (pinfunction "3_3") (pintype "passive"))
      (node (ref "R36") (pin "2") (pinfunction "2_2") (pintype "passive"))
      (node (ref "R37") (pin "2") (pinfunction "2_2") (pintype "passive"))
      (node (ref "R38") (pin "2") (pinfunction "2_2") (pintype "passive"))
    )
    (net (code "92") (name "GND") (class "Default")
      (node (ref "C15") (pin "2") (pinfunction "2_2") (pintype "passive"))
      (node (ref "C16") (pin "2") (pinfunction "2_2") (pintype "passive"))
      (node (ref "C17") (pin "2") (pinfunction "2_2") (pintype "passive"))
      (node (ref "C18") (pin "1") (pinfunction "1_1") (pintype "passive"))
      (node (ref "C19") (pin "1") (pinfunction "1_1") (pintype "passive"))
      (node (ref "C20") (pin "1") (pinfunction "1_1") (pintype "passive"))
      (node (ref "C24") (pin "1") (pinfunction "1_1") (pintype "passive"))
      (node (ref "C25") (pin "1") (pinfunction "1_1") (pintype "passive"))
      (node (ref "C26") (pin "1") (pinfunction "1_1") (pintype "passive"))
      (node (ref "C27") (pin "1") (pinfunction "1_1") (pintype "passive"))
      (node (ref "C28") (pin "1") (pinfunction "1_1") (pintype "passive"))
      (node (ref "C29") (pin "1") (pinfunction "1_1") (pintype "passive"))
      (node (ref "C30") (pin "2") (pinfunction "2_2") (pintype "passive"))
      (node (ref "C31") (pin "2") (pinfunction "2_2") (pintype "passive"))
      (node (ref "C32") (pin "2") (pinfunction "2_2") (pintype "passive"))
      (node (ref "D2") (pin "2") (pinfunction "A_2") (pintype "passive"))
      (node (ref "D3") (pin "2") (pinfunction "A_2") (pintype "passive"))
      (node (ref "D4") (pin "2") (pinfunction "A_2") (pintype "passive"))
      (node (ref "D5") (pin "2") (pinfunction "A_2") (pintype "passive"))
      (node (ref "D6") (pin "2") (pinfunction "A_2") (pintype "passive"))
      (node (ref "D7") (pin "2") (pinfunction "A_2") (pintype "passive"))
      (node (ref "J2") (pin "4") (pinfunction "4_4") (pintype "passive"))
      (node (ref "J3") (pin "4") (pinfunction "4_4") (pintype "passive"))
      (node (ref "P4") (pin "5") (pinfunction "5_5") (pintype "passive"))
      (node (ref "R32") (pin "1") (pinfunction "1_1") (pintype "passive"))
      (node (ref "R33") (pin "1") (pinfunction "1_1") (pintype "passive"))
      (node (ref "R34") (pin "1") (pinfunction "1_1") (pintype "passive"))
      (node (ref "R35") (pin "1") (pinfunction "1_1") (pintype "passive"))
      (node (ref "U2") (pin "12") (pinfunction "GND_12") (pintype "power_in"))
      (node (ref "U3") (pin "12") (pinfunction "GND_12") (pintype "power_in"))
      (node (ref "U4") (pin "12") (pinfunction "GND_12") (pintype "power_in"))
    )
    (net (code "93") (name "GVDD") (class "Default")
      (node (ref "D13") (pin "2") (pinfunction "A_2") (pintype "passive"))
    )
    (net (code "94") (name "HALL_PWR") (class "Default")
      (node (ref "P4") (pin "1") (pinfunction "1_1") (pintype "passive"))
      (node (ref "P5") (pin "2") (pinfunction "2_2") (pintype "passive"))
    )
    (net (code "95") (name "MCU_LED") (class "Default")
      (node (ref "D14") (pin "2") (pinfunction "A_2") (pintype "passive"))
      (node (ref "J4") (pin "19") (pinfunction "19_19") (pintype "passive"))
    )
    (net (code "96") (name "Net-(C21-Pad1)") (class "Default")
      (node (ref "C21") (pin "1") (pinfunction "1_1") (pintype "passive"))
      (node (ref "R15") (pin "2") (pinfunction "2_2") (pintype "passive"))
    )
    (net (code "97") (name "Net-(C22-Pad1)") (class "Default")
      (node (ref "C22") (pin "1") (pinfunction "1_1") (pintype "passive"))
      (node (ref "R16") (pin "2") (pinfunction "2_2") (pintype "passive"))
    )
    (net (code "98") (name "Net-(C23-Pad1)") (class "Default")
      (node (ref "C23") (pin "1") (pinfunction "1_1") (pintype "passive"))
      (node (ref "R17") (pin "2") (pinfunction "2_2") (pintype "passive"))
    )
    (net (code "99") (name "Net-(D8-C)") (class "Default")
      (node (ref "D8") (pin "1") (pinfunction "C_1") (pintype "passive"))
      (node (ref "R29") (pin "2") (pinfunction "2_2") (pintype "passive"))
    )
    (net (code "100") (name "Net-(D9-C)") (class "Default")
      (node (ref "D9") (pin "1") (pinfunction "C_1") (pintype "passive"))
      (node (ref "R30") (pin "2") (pinfunction "2_2") (pintype "passive"))
    )
    (net (code "101") (name "Net-(D10-C)") (class "Default")
      (node (ref "D10") (pin "1") (pinfunction "C_1") (pintype "passive"))
      (node (ref "R31") (pin "2") (pinfunction "2_2") (pintype "passive"))
    )
    (net (code "102") (name "Net-(D11-C)") (class "Default")
      (node (ref "D11") (pin "1") (pinfunction "C_1") (pintype "passive"))
      (node (ref "R32") (pin "2") (pinfunction "2_2") (pintype "passive"))
    )
    (net (code "103") (name "Net-(D12-C)") (class "Default")
      (node (ref "D12") (pin "1") (pinfunction "C_1") (pintype "passive"))
      (node (ref "R33") (pin "2") (pinfunction "2_2") (pintype "passive"))
    )
    (net (code "104") (name "Net-(D13-C)") (class "Default")
      (node (ref "D13") (pin "1") (pinfunction "C_1") (pintype "passive"))
      (node (ref "R34") (pin "2") (pinfunction "2_2") (pintype "passive"))
    )
    (net (code "105") (name "Net-(D14-C)") (class "Default")
      (node (ref "D14") (pin "1") (pinfunction "C_1") (pintype "passive"))
      (node (ref "R35") (pin "2") (pinfunction "2_2") (pintype "passive"))
    )
    (net (code "106") (name "Net-(D15-A)") (class "Default")
      (node (ref "D15") (pin "2") (pinfunction "A_2") (pintype "passive"))
      (node (ref "J4") (pin "4") (pinfunction "4_4") (pintype "passive"))
    )
    (net (code "107") (name "Net-(D16-A)") (class "Default")
      (node (ref "D16") (pin "2") (pinfunction "A_2") (pintype "passive"))
      (node (ref "J4") (pin "12") (pinfunction "12_12") (pintype "passive"))
    )
    (net (code "108") (name "Net-(D17-A)") (class "Default")
      (node (ref "D17") (pin "2") (pinfunction "A_2") (pintype "passive"))
      (node (ref "J4") (pin "14") (pinfunction "14_14") (pintype "passive"))
    )
    (net (code "109") (name "Net-(J2-Pad1)") (class "Default")
      (node (ref "J2") (pin "1") (pinfunction "1_1") (pintype "passive"))
      (node (ref "R24") (pin "2") (pinfunction "2_2") (pintype "passive"))
    )
    (net (code "110") (name "Net-(J2-Pad3)") (class "Default")
      (node (ref "J2") (pin "3") (pinfunction "3_3") (pintype "passive"))
      (node (ref "R25") (pin "2") (pinfunction "2_2") (pintype "passive"))
    )
    (net (code "111") (name "Net-(J2-Pad15)") (class "Default")
      (node (ref "J2") (pin "15") (pinfunction "15_15") (pintype "passive"))
      (node (ref "R27") (pin "2") (pinfunction "2_2") (pintype "passive"))
    )
    (net (code "112") (name "Net-(J3-Pad3)") (class "Default")
      (node (ref "J3") (pin "3") (pinfunction "3_3") (pintype "passive"))
      (node (ref "R26") (pin "2") (pinfunction "2_2") (pintype "passive"))
    )
    (net (code "113") (name "Net-(J3-Pad15)") (class "Default")
      (node (ref "J3") (pin "15") (pinfunction "15_15") (pintype "passive"))
      (node (ref "R28") (pin "2") (pinfunction "2_2") (pintype "passive"))
    )
    (net (code "114") (name "PVDD") (class "Default")
      (node (ref "D12") (pin "2") (pinfunction "A_2") (pintype "passive"))
    )
    (net (code "115") (name "unconnected-(D15-K-Pad1)") (class "Default")
      (node (ref "D15") (pin "1") (pinfunction "K_1") (pintype "passive"))
    )
    (net (code "116") (name "unconnected-(D16-K-Pad1)") (class "Default")
      (node (ref "D16") (pin "1") (pinfunction "K_1") (pintype "passive"))
    )
    (net (code "117") (name "unconnected-(D17-K-Pad1)") (class "Default")
      (node (ref "D17") (pin "1") (pinfunction "K_1") (pintype "passive"))
    )
    (net (code "118") (name "unconnected-(J2-Pad2)") (class "Default")
      (node (ref "J2") (pin "2") (pinfunction "2_2") (pintype "passive"))
    )
    (net (code "119") (name "unconnected-(J2-Pad5)") (class "Default")
      (node (ref "J2") (pin "5") (pinfunction "5_5") (pintype "passive"))
    )
    (net (code "120") (name "unconnected-(J2-Pad9)") (class "Default")
      (node (ref "J2") (pin "9") (pinfunction "9_9") (pintype "passive"))
    )
    (net (code "121") (name "unconnected-(J2-Pad13)") (class "Default")
      (node (ref "J2") (pin "13") (pinfunction "13_13") (pintype "passive"))
    )
    (net (code "122") (name "unconnected-(J2-Pad17)") (class "Default")
      (node (ref "J2") (pin "17") (pinfunction "17_17") (pintype "passive"))
    )
    (net (code "123") (name "unconnected-(J2-Pad19)") (class "Default")
      (node (ref "J2") (pin "19") (pinfunction "19_19") (pintype "passive"))
    )
    (net (code "124") (name "unconnected-(J3-Pad2)") (class "Default")
      (node (ref "J3") (pin "2") (pinfunction "2_2") (pintype "passive"))
    )
    (net (code "125") (name "unconnected-(J3-Pad5)") (class "Default")
      (node (ref "J3") (pin "5") (pinfunction "5_5") (pintype "passive"))
    )
    (net (code "126") (name "unconnected-(J3-Pad7)") (class "Default")
      (node (ref "J3") (pin "7") (pinfunction "7_7") (pintype "passive"))
    )
    (net (code "127") (name "unconnected-(J3-Pad9)") (class "Default")
      (node (ref "J3") (pin "9") (pinfunction "9_9") (pintype "passive"))
    )
    (net (code "128") (name "unconnected-(J3-Pad12)") (class "Default")
      (node (ref "J3") (pin "12") (pinfunction "12_12") (pintype "passive"))
    )
    (net (code "129") (name "unconnected-(J3-Pad13)") (class "Default")
      (node (ref "J3") (pin "13") (pinfunction "13_13") (pintype "passive"))
    )
    (net (code "130") (name "unconnected-(J3-Pad17)") (class "Default")
      (node (ref "J3") (pin "17") (pinfunction "17_17") (pintype "passive"))
    )
    (net (code "131") (name "unconnected-(J3-Pad19)") (class "Default")
      (node (ref "J3") (pin "19") (pinfunction "19_19") (pintype "passive"))
    )
    (net (code "132") (name "unconnected-(J4-Pad2)") (class "Default")
      (node (ref "J4") (pin "2") (pinfunction "2_2") (pintype "passive"))
    )
    (net (code "133") (name "unconnected-(J4-Pad6)") (class "Default")
      (node (ref "J4") (pin "6") (pinfunction "6_6") (pintype "passive"))
    )
    (net (code "134") (name "unconnected-(J4-Pad8)") (class "Default")
      (node (ref "J4") (pin "8") (pinfunction "8_8") (pintype "passive"))
    )
    (net (code "135") (name "unconnected-(J4-Pad10)") (class "Default")
      (node (ref "J4") (pin "10") (pinfunction "10_10") (pintype "passive"))
    )
    (net (code "136") (name "unconnected-(J4-Pad17)") (class "Default")
      (node (ref "J4") (pin "17") (pinfunction "17_17") (pintype "passive"))
    )
    (net (code "137") (name "unconnected-(J5-Pad2)") (class "Default")
      (node (ref "J5") (pin "2") (pinfunction "2_2") (pintype "passive"))
    )
    (net (code "138") (name "unconnected-(J5-Pad4)") (class "Default")
      (node (ref "J5") (pin "4") (pinfunction "4_4") (pintype "passive"))
    )
    (net (code "139") (name "unconnected-(J5-Pad6)") (class "Default")
      (node (ref "J5") (pin "6") (pinfunction "6_6") (pintype "passive"))
    )
    (net (code "140") (name "unconnected-(J5-Pad8)") (class "Default")
      (node (ref "J5") (pin "8") (pinfunction "8_8") (pintype "passive"))
    )
    (net (code "141") (name "unconnected-(J5-Pad10)") (class "Default")
      (node (ref "J5") (pin "10") (pinfunction "10_10") (pintype "passive"))
    )
    (net (code "142") (name "unconnected-(J5-Pad12)") (class "Default")
      (node (ref "J5") (pin "12") (pinfunction "12_12") (pintype "passive"))
    )
    (net (code "143") (name "unconnected-(J5-Pad14)") (class "Default")
      (node (ref "J5") (pin "14") (pinfunction "14_14") (pintype "passive"))
    )
    (net (code "144") (name "unconnected-(J5-Pad16)") (class "Default")
      (node (ref "J5") (pin "16") (pinfunction "16_16") (pintype "passive"))
    )
    (net (code "145") (name "unconnected-(J5-Pad17)") (class "Default")
      (node (ref "J5") (pin "17") (pinfunction "17_17") (pintype "passive"))
    )
    (net (code "146") (name "unconnected-(J5-Pad18)") (class "Default")
      (node (ref "J5") (pin "18") (pinfunction "18_18") (pintype "passive"))
    )
    (net (code "147") (name "unconnected-(J5-Pad19)") (class "Default")
      (node (ref "J5") (pin "19") (pinfunction "19_19") (pintype "passive"))
    )
    (net (code "148") (name "unconnected-(J5-Pad20)") (class "Default")
      (node (ref "J5") (pin "20") (pinfunction "20_20") (pintype "passive"))
    )
    (net (code "149") (name "unconnected-(P5-Pad1)") (class "Default")
      (node (ref "P5") (pin "1") (pinfunction "1_1") (pintype "passive"))
    )
  )
)
